# DetectorHardware.net
KiCad netlist of a schematic drawn in EAGLE
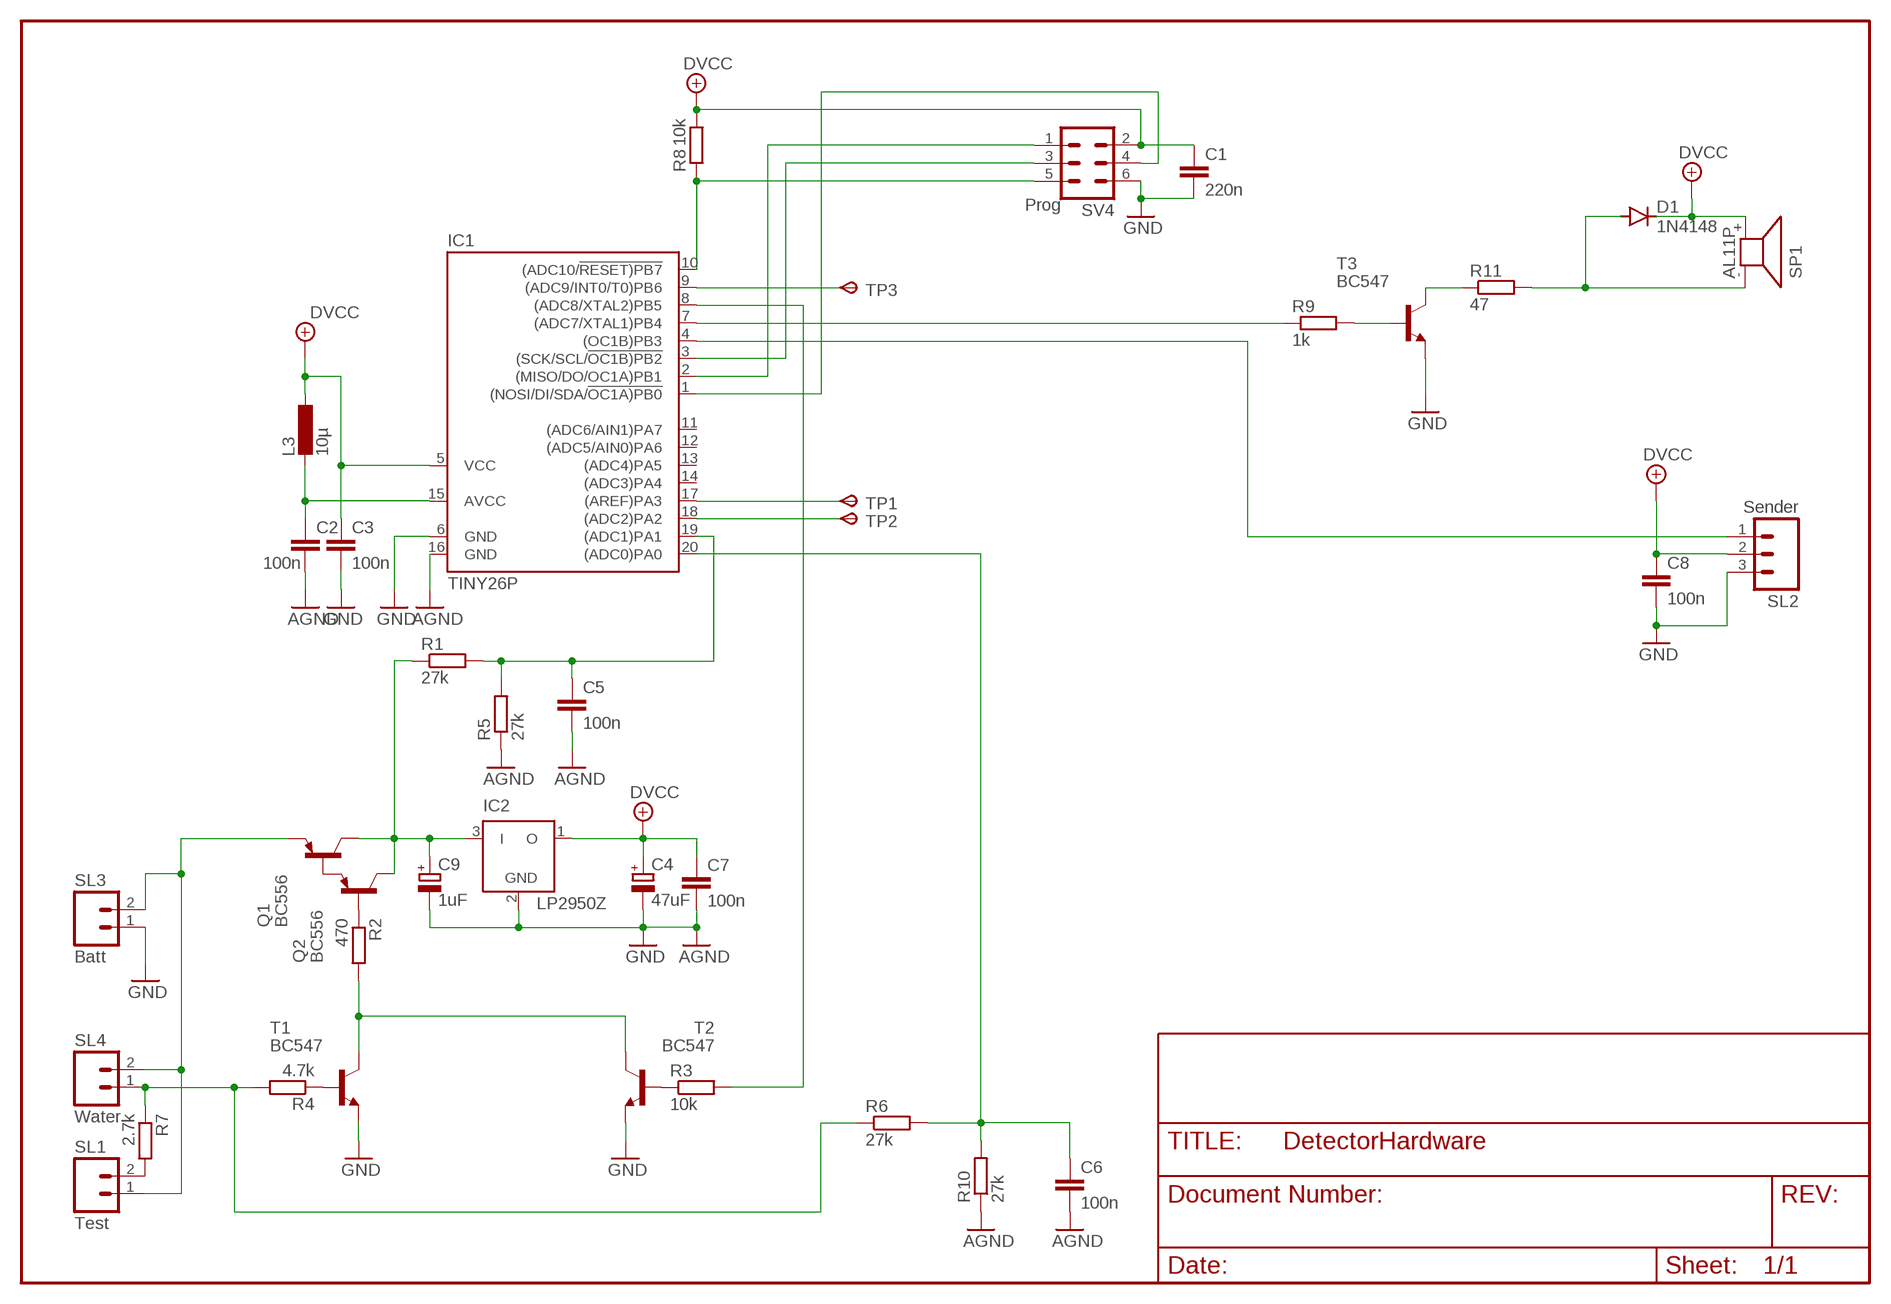
[diagram p0: schematic, sheet 1]

(export (version "E")
  (design (tool "Eeschema 10.0.6"))
  (components
    (comp (ref "C1")
      (value "220n")
      (footprint "eagle-import:C025-024X044")
      (libsource (lib "eagle-import") (part "C-EU025-024X044"))
    )
    (comp (ref "C2")
      (value "100n")
      (footprint "eagle-import:C025-024X044")
      (libsource (lib "eagle-import") (part "C-EU025-024X044"))
    )
    (comp (ref "C3")
      (value "100n")
      (footprint "eagle-import:C025-024X044")
      (libsource (lib "eagle-import") (part "C-EU025-024X044"))
    )
    (comp (ref "C4")
      (value "47uF")
      (footprint "eagle-import:E2,5-6")
      (libsource (lib "eagle-import") (part "CPOL-EUE2.5-6"))
    )
    (comp (ref "C5")
      (value "100n")
      (footprint "eagle-import:C025-024X044")
      (libsource (lib "eagle-import") (part "C-EU025-024X044"))
    )
    (comp (ref "C6")
      (value "100n")
      (footprint "eagle-import:C025-024X044")
      (libsource (lib "eagle-import") (part "C-EU025-024X044"))
    )
    (comp (ref "C7")
      (value "100n")
      (footprint "eagle-import:C025-024X044")
      (libsource (lib "eagle-import") (part "C-EU025-024X044"))
    )
    (comp (ref "C8")
      (value "100n")
      (footprint "eagle-import:C025-024X044")
      (libsource (lib "eagle-import") (part "C-EU025-024X044"))
    )
    (comp (ref "C9")
      (value "1uF")
      (footprint "eagle-import:E2,5-6")
      (libsource (lib "eagle-import") (part "CPOL-EUE2.5-6"))
    )
    (comp (ref "D1")
      (value "1N4148")
      (footprint "eagle-import:D-5")
      (libsource (lib "eagle-import") (part "DIODE-D-5"))
    )
    (comp (ref "IC1")
      (value "TINY26P")
      (footprint "eagle-import:DIL20")
      (libsource (lib "eagle-import") (part "TINY26P"))
    )
    (comp (ref "IC2")
      (value "LP2950Z")
      (footprint "eagle-import:TO92")
      (libsource (lib "eagle-import") (part "LP2950Z"))
    )
    (comp (ref "L3")
      (value "10µ")
      (footprint "eagle-import:0204_5")
      (libsource (lib "eagle-import") (part "L-EU0204/5"))
    )
    (comp (ref "Q1")
      (value "BC556")
      (footprint "eagle-import:TO92-EBC")
      (libsource (lib "eagle-import") (part "BC556"))
    )
    (comp (ref "Q2")
      (value "BC556")
      (footprint "eagle-import:TO92-EBC")
      (libsource (lib "eagle-import") (part "BC556"))
    )
    (comp (ref "R1")
      (value "27k")
      (footprint "eagle-import:0204_5")
      (libsource (lib "eagle-import") (part "R-EU_0204/5"))
    )
    (comp (ref "R2")
      (value "470")
      (footprint "eagle-import:0204_5")
      (libsource (lib "eagle-import") (part "R-EU_0204/5"))
    )
    (comp (ref "R3")
      (value "10k")
      (footprint "eagle-import:0204_5")
      (libsource (lib "eagle-import") (part "R-EU_0204/5"))
    )
    (comp (ref "R4")
      (value "4.7k")
      (footprint "eagle-import:0204_5")
      (libsource (lib "eagle-import") (part "R-EU_0204/5"))
    )
    (comp (ref "R5")
      (value "27k")
      (footprint "eagle-import:0204_5")
      (libsource (lib "eagle-import") (part "R-EU_0204/5"))
    )
    (comp (ref "R6")
      (value "27k")
      (footprint "eagle-import:0204_5")
      (libsource (lib "eagle-import") (part "R-EU_0204/5"))
    )
    (comp (ref "R7")
      (value "2.7k")
      (footprint "eagle-import:0204_5")
      (libsource (lib "eagle-import") (part "R-EU_0204/5"))
    )
    (comp (ref "R8")
      (value "10k")
      (footprint "eagle-import:0204_5")
      (libsource (lib "eagle-import") (part "R-EU_0204/5"))
    )
    (comp (ref "R9")
      (value "1k")
      (footprint "eagle-import:0204_5")
      (libsource (lib "eagle-import") (part "R-EU_0204/5"))
    )
    (comp (ref "R10")
      (value "27k")
      (footprint "eagle-import:0204_5")
      (libsource (lib "eagle-import") (part "R-EU_0204/5"))
    )
    (comp (ref "R11")
      (value "47")
      (footprint "eagle-import:0204_5")
      (libsource (lib "eagle-import") (part "R-EU_0204/5"))
    )
    (comp (ref "SL1")
      (value "Test")
      (footprint "eagle-import:02P")
      (libsource (lib "eagle-import") (part "M02"))
    )
    (comp (ref "SL2")
      (value "Sender")
      (footprint "eagle-import:03P")
      (libsource (lib "eagle-import") (part "M03"))
    )
    (comp (ref "SL3")
      (value "Batt")
      (footprint "eagle-import:02P")
      (libsource (lib "eagle-import") (part "M02"))
    )
    (comp (ref "SL4")
      (value "Water")
      (footprint "eagle-import:02P")
      (libsource (lib "eagle-import") (part "M02"))
    )
    (comp (ref "SP1")
      (value "AL11P")
      (footprint "eagle-import:AL11P")
      (libsource (lib "eagle-import") (part "AL11P"))
    )
    (comp (ref "SV4")
      (value "Prog")
      (footprint "eagle-import:MA03-2")
      (libsource (lib "eagle-import") (part "MA03-2"))
    )
    (comp (ref "T1")
      (value "BC547")
      (footprint "eagle-import:TO92")
      (libsource (lib "eagle-import") (part "BC547"))
    )
    (comp (ref "T2")
      (value "BC547")
      (footprint "eagle-import:TO92")
      (libsource (lib "eagle-import") (part "BC547"))
    )
    (comp (ref "T3")
      (value "BC547")
      (footprint "eagle-import:TO92")
      (libsource (lib "eagle-import") (part "BC547"))
    )
    (comp (ref "TP1")
      (value "TPSB1,27")
      (footprint "eagle-import:B1,27")
      (libsource (lib "eagle-import") (part "TPSB1,27"))
    )
    (comp (ref "TP2")
      (value "TPSB1,27")
      (footprint "eagle-import:B1,27")
      (libsource (lib "eagle-import") (part "TPSB1,27"))
    )
    (comp (ref "TP3")
      (value "TPSB1,27")
      (footprint "eagle-import:B1,27")
      (libsource (lib "eagle-import") (part "TPSB1,27"))
    )
  )
  (nets
    (net (code "1") (name "AGND") (class "Default")
      (node (ref "C1") (pin "2") (pinfunction "2_2") (pintype "passive"))
      (node (ref "C2") (pin "2") (pinfunction "2_2") (pintype "passive"))
      (node (ref "C3") (pin "2") (pinfunction "2_2") (pintype "passive"))
      (node (ref "C4") (pin "-") (pinfunction "-_-") (pintype "passive"))
      (node (ref "C5") (pin "2") (pinfunction "2_2") (pintype "passive"))
      (node (ref "C6") (pin "2") (pinfunction "2_2") (pintype "passive"))
      (node (ref "C7") (pin "2") (pinfunction "2_2") (pintype "passive"))
      (node (ref "C8") (pin "2") (pinfunction "2_2") (pintype "passive"))
      (node (ref "C9") (pin "-") (pinfunction "-_-") (pintype "passive"))
      (node (ref "IC1") (pin "16") (pinfunction "GND_16") (pintype "power_in"))
      (node (ref "IC1") (pin "6") (pinfunction "GND_6") (pintype "power_in"))
      (node (ref "IC2") (pin "2") (pinfunction "GND_2") (pintype "power_in"))
      (node (ref "R10") (pin "1") (pinfunction "1_1") (pintype "passive"))
      (node (ref "R5") (pin "1") (pinfunction "1_1") (pintype "passive"))
      (node (ref "SL2") (pin "3") (pinfunction "3_3") (pintype "passive"))
      (node (ref "SL3") (pin "1") (pinfunction "1_1") (pintype "passive"))
      (node (ref "SV4") (pin "6") (pinfunction "6_6") (pintype "passive"))
      (node (ref "T1") (pin "1") (pinfunction "E_1") (pintype "passive"))
      (node (ref "T2") (pin "1") (pinfunction "E_1") (pintype "passive"))
      (node (ref "T3") (pin "1") (pinfunction "E_1") (pintype "passive"))
    )
    (net (code "2") (name "DVCC") (class "Default")
      (node (ref "C1") (pin "1") (pinfunction "1_1") (pintype "passive"))
      (node (ref "C3") (pin "1") (pinfunction "1_1") (pintype "passive"))
      (node (ref "C4") (pin "+") (pinfunction "+_+") (pintype "passive"))
      (node (ref "C7") (pin "1") (pinfunction "1_1") (pintype "passive"))
      (node (ref "C8") (pin "1") (pinfunction "1_1") (pintype "passive"))
      (node (ref "D1") (pin "C") (pinfunction "C_C") (pintype "passive"))
      (node (ref "IC1") (pin "5") (pinfunction "VCC_5") (pintype "power_in"))
      (node (ref "IC2") (pin "1") (pinfunction "O_1") (pintype "input"))
      (node (ref "L3") (pin "1") (pinfunction "1_1") (pintype "passive"))
      (node (ref "R8") (pin "2") (pinfunction "2_2") (pintype "passive"))
      (node (ref "SL2") (pin "2") (pinfunction "2_2") (pintype "passive"))
      (node (ref "SP1") (pin "+") (pinfunction "2_+") (pintype "passive"))
      (node (ref "SV4") (pin "2") (pinfunction "2_2") (pintype "passive"))
    )
    (net (code "3") (name "Net-(IC1-(ADC0)PA0)") (class "Default")
      (node (ref "C6") (pin "1") (pinfunction "1_1") (pintype "passive"))
      (node (ref "IC1") (pin "20") (pinfunction "(ADC0)PA0_20") (pintype "bidirectional"))
      (node (ref "R10") (pin "2") (pinfunction "2_2") (pintype "passive"))
      (node (ref "R6") (pin "2") (pinfunction "2_2") (pintype "passive"))
    )
    (net (code "4") (name "Net-(IC1-(ADC1)PA1)") (class "Default")
      (node (ref "C5") (pin "1") (pinfunction "1_1") (pintype "passive"))
      (node (ref "IC1") (pin "19") (pinfunction "(ADC1)PA1_19") (pintype "bidirectional"))
      (node (ref "R1") (pin "2") (pinfunction "2_2") (pintype "passive"))
      (node (ref "R5") (pin "2") (pinfunction "2_2") (pintype "passive"))
    )
    (net (code "5") (name "Net-(IC1-(ADC2)PA2)") (class "Default")
      (node (ref "IC1") (pin "18") (pinfunction "(ADC2)PA2_18") (pintype "bidirectional"))
      (node (ref "TP2") (pin "TP") (pinfunction "PP_TP") (pintype "input"))
    )
    (net (code "6") (name "Net-(IC1-(ADC7{slash}XTAL1)PB4)") (class "Default")
      (node (ref "IC1") (pin "7") (pinfunction "(ADC7/XTAL1)PB4_7") (pintype "bidirectional"))
      (node (ref "R9") (pin "1") (pinfunction "1_1") (pintype "passive"))
    )
    (net (code "7") (name "Net-(IC1-(ADC8{slash}XTAL2)PB5)") (class "Default")
      (node (ref "IC1") (pin "8") (pinfunction "(ADC8/XTAL2)PB5_8") (pintype "bidirectional"))
      (node (ref "R3") (pin "2") (pinfunction "2_2") (pintype "passive"))
    )
    (net (code "8") (name "Net-(IC1-(ADC9{slash}INT0{slash}T0)PB6)") (class "Default")
      (node (ref "IC1") (pin "9") (pinfunction "(ADC9/INT0/T0)PB6_9") (pintype "bidirectional"))
      (node (ref "TP3") (pin "TP") (pinfunction "PP_TP") (pintype "input"))
    )
    (net (code "9") (name "Net-(IC1-(ADC10{slash}~{RESET})PB7)") (class "Default")
      (node (ref "IC1") (pin "10") (pinfunction "(ADC10/~{RESET})PB7_10") (pintype "bidirectional"))
      (node (ref "R8") (pin "1") (pinfunction "1_1") (pintype "passive"))
      (node (ref "SV4") (pin "5") (pinfunction "5_5") (pintype "passive"))
    )
    (net (code "10") (name "Net-(IC1-(AREF)PA3)") (class "Default")
      (node (ref "IC1") (pin "17") (pinfunction "(AREF)PA3_17") (pintype "bidirectional"))
      (node (ref "TP1") (pin "TP") (pinfunction "PP_TP") (pintype "input"))
    )
    (net (code "11") (name "Net-(IC1-(MISO{slash}DO{slash}OC1A)PB1)") (class "Default")
      (node (ref "IC1") (pin "2") (pinfunction "(MISO/DO/OC1A)PB1_2") (pintype "bidirectional"))
      (node (ref "SV4") (pin "1") (pinfunction "1_1") (pintype "passive"))
    )
    (net (code "12") (name "Net-(IC1-(NOSI{slash}DI{slash}SDA{slash}~{OC1A})PB0)") (class "Default")
      (node (ref "IC1") (pin "1") (pinfunction "(NOSI/DI/SDA/~{OC1A})PB0_1") (pintype "bidirectional"))
      (node (ref "SV4") (pin "4") (pinfunction "4_4") (pintype "passive"))
    )
    (net (code "13") (name "Net-(IC1-(OC1B)PB3)") (class "Default")
      (node (ref "IC1") (pin "4") (pinfunction "(OC1B)PB3_4") (pintype "bidirectional"))
      (node (ref "SL2") (pin "1") (pinfunction "1_1") (pintype "passive"))
    )
    (net (code "14") (name "Net-(IC1-(SCK{slash}SCL{slash}~{OC1B})PB2)") (class "Default")
      (node (ref "IC1") (pin "3") (pinfunction "(SCK/SCL/~{OC1B})PB2_3") (pintype "bidirectional"))
      (node (ref "SV4") (pin "3") (pinfunction "3_3") (pintype "passive"))
    )
    (net (code "15") (name "Net-(IC1-AVCC)") (class "Default")
      (node (ref "C2") (pin "1") (pinfunction "1_1") (pintype "passive"))
      (node (ref "IC1") (pin "15") (pinfunction "AVCC_15") (pintype "power_in"))
      (node (ref "L3") (pin "2") (pinfunction "2_2") (pintype "passive"))
    )
    (net (code "16") (name "Net-(IC2-I)") (class "Default")
      (node (ref "C9") (pin "+") (pinfunction "+_+") (pintype "passive"))
      (node (ref "IC2") (pin "3") (pinfunction "I_3") (pintype "input"))
      (node (ref "Q1") (pin "C") (pinfunction "C_C") (pintype "passive"))
      (node (ref "Q2") (pin "C") (pinfunction "C_C") (pintype "passive"))
      (node (ref "R1") (pin "1") (pinfunction "1_1") (pintype "passive"))
    )
    (net (code "17") (name "Net-(Q1-PadB)") (class "Default")
      (node (ref "Q1") (pin "B") (pinfunction "B_B") (pintype "passive"))
      (node (ref "Q2") (pin "E") (pinfunction "E_E") (pintype "passive"))
    )
    (net (code "18") (name "Net-(Q1-PadE)") (class "Default")
      (node (ref "Q1") (pin "E") (pinfunction "E_E") (pintype "passive"))
      (node (ref "SL1") (pin "1") (pinfunction "1_1") (pintype "passive"))
      (node (ref "SL3") (pin "2") (pinfunction "2_2") (pintype "passive"))
      (node (ref "SL4") (pin "2") (pinfunction "2_2") (pintype "passive"))
    )
    (net (code "19") (name "Net-(Q2-PadB)") (class "Default")
      (node (ref "Q2") (pin "B") (pinfunction "B_B") (pintype "passive"))
      (node (ref "R2") (pin "1") (pinfunction "1_1") (pintype "passive"))
    )
    (net (code "20") (name "Net-(R4-Pad2)") (class "Default")
      (node (ref "R4") (pin "2") (pinfunction "2_2") (pintype "passive"))
      (node (ref "R6") (pin "1") (pinfunction "1_1") (pintype "passive"))
      (node (ref "R7") (pin "1") (pinfunction "1_1") (pintype "passive"))
      (node (ref "SL4") (pin "1") (pinfunction "1_1") (pintype "passive"))
    )
    (net (code "21") (name "Net-(R7-Pad2)") (class "Default")
      (node (ref "R7") (pin "2") (pinfunction "2_2") (pintype "passive"))
      (node (ref "SL1") (pin "2") (pinfunction "2_2") (pintype "passive"))
    )
    (net (code "22") (name "Net-(SP1-1)") (class "Default")
      (node (ref "D1") (pin "A") (pinfunction "A_A") (pintype "passive"))
      (node (ref "R11") (pin "2") (pinfunction "2_2") (pintype "passive"))
      (node (ref "SP1") (pin "-") (pinfunction "1_-") (pintype "passive"))
    )
    (net (code "23") (name "Net-(T1-B)") (class "Default")
      (node (ref "R4") (pin "1") (pinfunction "1_1") (pintype "passive"))
      (node (ref "T1") (pin "2") (pinfunction "B_2") (pintype "passive"))
    )
    (net (code "24") (name "Net-(T1-C)") (class "Default")
      (node (ref "R2") (pin "2") (pinfunction "2_2") (pintype "passive"))
      (node (ref "T1") (pin "3") (pinfunction "C_3") (pintype "passive"))
      (node (ref "T2") (pin "3") (pinfunction "C_3") (pintype "passive"))
    )
    (net (code "25") (name "Net-(T2-B)") (class "Default")
      (node (ref "R3") (pin "1") (pinfunction "1_1") (pintype "passive"))
      (node (ref "T2") (pin "2") (pinfunction "B_2") (pintype "passive"))
    )
    (net (code "26") (name "Net-(T3-B)") (class "Default")
      (node (ref "R9") (pin "2") (pinfunction "2_2") (pintype "passive"))
      (node (ref "T3") (pin "2") (pinfunction "B_2") (pintype "passive"))
    )
    (net (code "27") (name "Net-(T3-C)") (class "Default")
      (node (ref "R11") (pin "1") (pinfunction "1_1") (pintype "passive"))
      (node (ref "T3") (pin "3") (pinfunction "C_3") (pintype "passive"))
    )
    (net (code "28") (name "unconnected-(IC1-(ADC3)PA4-Pad14)") (class "Default")
      (node (ref "IC1") (pin "14") (pinfunction "(ADC3)PA4_14") (pintype "bidirectional"))
    )
    (net (code "29") (name "unconnected-(IC1-(ADC4)PA5-Pad13)") (class "Default")
      (node (ref "IC1") (pin "13") (pinfunction "(ADC4)PA5_13") (pintype "bidirectional"))
    )
    (net (code "30") (name "unconnected-(IC1-(ADC5{slash}AIN0)PA6-Pad12)") (class "Default")
      (node (ref "IC1") (pin "12") (pinfunction "(ADC5/AIN0)PA6_12") (pintype "bidirectional"))
    )
    (net (code "31") (name "unconnected-(IC1-(ADC6{slash}AIN1)PA7-Pad11)") (class "Default")
      (node (ref "IC1") (pin "11") (pinfunction "(ADC6/AIN1)PA7_11") (pintype "bidirectional"))
    )
  )
)
